# Signal_TX.net
KiCad netlist of a schematic drawn in Altium Designer
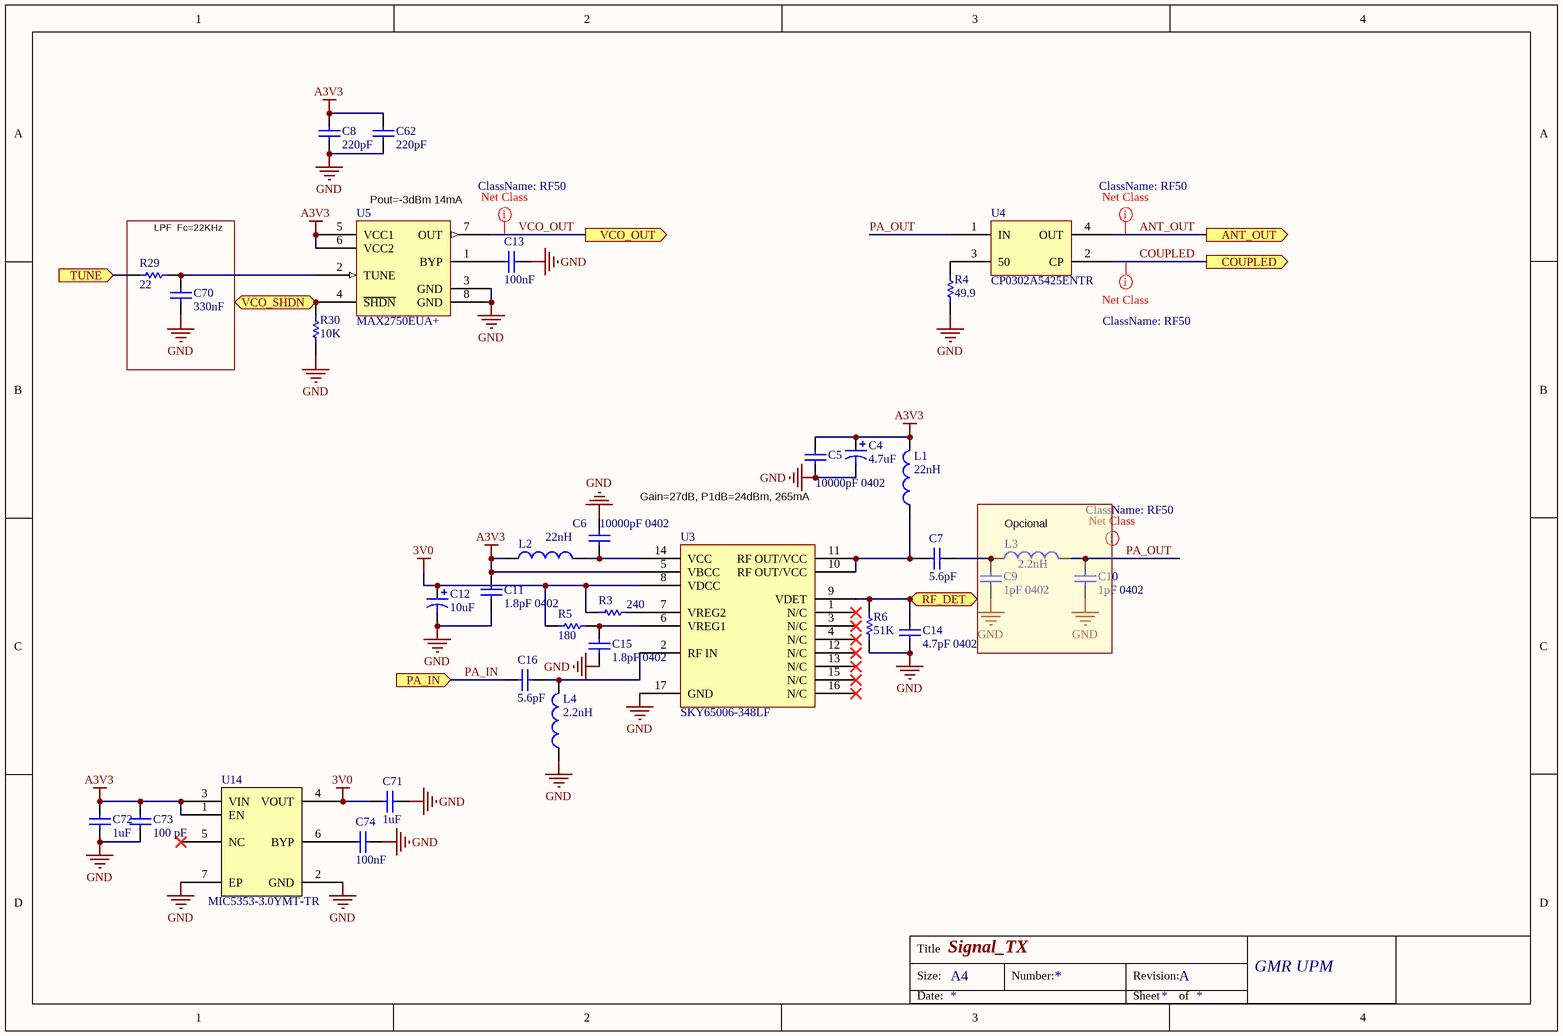
[diagram p0: Signal_TX.SchDoc]

(export (version "E")
  (design (tool "Eeschema 10.0.6"))
  (components
    (comp (ref "C4")
      (value "4.7uF")
      (footprint "0603 Cap")
      (description "CAP TANT 4.7UF 10V 20% 0603")
      (fields
        (field (name "MANUFACTURER") "AVX Corporation")
        (field (name "MANUFACTURER PART NUMBER") "F981A475MMA")
      )
      (libsource (lib "Componentes_base") (part "F981A475MMA"))
    )
    (comp (ref "C5")
      (value "10000pF 0402")
      (footprint "RESC1005X04L")
      (description "CAP CER 10000PF 25V X7R 0402")
      (fields
        (field (name "MANUFACTURER") "Murata Electronics North America")
        (field (name "MANUFACTURER PART NUMBER") "GRM155R71E103KA01J")
      )
      (libsource (lib "Componentes_base") (part "GRM155R71E103KA01J"))
    )
    (comp (ref "C6")
      (value "10000pF 0402")
      (footprint "RESC1005X04L")
      (description "CAP CER 10000PF 25V X7R 0402")
      (fields
        (field (name "MANUFACTURER") "Murata Electronics North America")
        (field (name "MANUFACTURER PART NUMBER") "GRM155R71E103KA01J")
      )
      (libsource (lib "Componentes_base") (part "GRM155R71E103KA01J"))
    )
    (comp (ref "C7")
      (value "5.6pF")
      (footprint "RESC1005X04L")
      (description "AVX - 04025A5R6CAT2A - COND, MLCC, C0G/NP0, 5.6PF, 50V, 0402")
      (fields (field (name "MANUFACTURER") "AVX") (field (name "MANUFACTURER PART NUMBER") "04025A5R6CAT2A"))
      (libsource (lib "Componentes_base") (part "04025A5R6CAT2A"))
    )
    (comp (ref "C8")
      (value "220pF")
      (footprint "0603 Cap")
      (description "CAP CER 220PF 50V X7R 0603")
      (fields
        (field (name "MANUFACTURER") "Samsung Electro-Mechanics America, Inc.")
        (field (name "MANUFACTURER PART NUMBER") "CL10B221KB8WPNC")
      )
      (libsource (lib "Componentes_base") (part "CL10B221KB8WPNC"))
    )
    (comp (ref "C9")
      (value "1pF 0402")
      (footprint "CAPC1005X05L")
      (description "CAP CER 1PF 50V C0G/NP0 0402")
      (libsource (lib "Componentes_base") (part "GRM1555C1H1R0CA01D"))
    )
    (comp (ref "C10")
      (value "1pF 0402")
      (footprint "CAPC1005X05L")
      (description "CAP CER 1PF 50V C0G/NP0 0402")
      (libsource (lib "Componentes_base") (part "GRM1555C1H1R0CA01D"))
    )
    (comp (ref "C11")
      (value "1.8pF 0402")
      (footprint "CAPC1005X05L")
      (description "CAP CER 1.8PF 50V C0G/NP0 0402")
      (fields
        (field (name "MANUFACTURER") "Murata Electronics North America")
        (field (name "MANUFACTURER PART NUMBER") "GRM1555C1H1R8CZ01D")
      )
      (libsource (lib "Componentes_base") (part "GRM1555C1H1R8CZ01D"))
    )
    (comp (ref "C12")
      (value "10uF")
      (footprint "CAPC3216X09L")
      (description "CAP TANT 10UF 6.3V 20% 1206")
      (fields
        (field (name "MANUFACTURER") "AVX Corporation")
        (field (name "MANUFACTURER PART NUMBER") "TAJA106M006RNJ")
      )
      (libsource (lib "Componentes_base") (part "TAJA106M006RNJ"))
    )
    (comp (ref "C13")
      (value "100nF")
      (footprint "0603 Cap")
      (description "CAP CER 0.1UF 16V X7R 0603")
      (fields
        (field (name "MANUFACTURER") "KEMET")
        (field (name "MANUFACTURER PART NUMBER") "C0603C104K4RACTU")
      )
      (libsource (lib "Componentes_base") (part "C0603C104K4RACTU"))
    )
    (comp (ref "C14")
      (value "4.7pF 0402")
      (footprint "RESC1005X04L")
      (description "CAP CER 4.7PF 50V C0G/NP0 0402")
      (fields
        (field (name "MANUFACTURER") "Murata Electronics North America")
        (field (name "MANUFACTURER PART NUMBER") "GRM1555C1H4R7CA01D")
      )
      (libsource (lib "Componentes_base") (part "GRM1555C1H4R7CA01D"))
    )
    (comp (ref "C15")
      (value "1.8pF 0402")
      (footprint "CAPC1005X05L")
      (description "CAP CER 1.8PF 50V C0G/NP0 0402")
      (fields
        (field (name "MANUFACTURER") "Murata Electronics North America")
        (field (name "MANUFACTURER PART NUMBER") "GRM1555C1H1R8CZ01D")
      )
      (libsource (lib "Componentes_base") (part "GRM1555C1H1R8CZ01D"))
    )
    (comp (ref "C16")
      (value "5.6pF")
      (footprint "RESC1005X04L")
      (description "AVX - 04025A5R6CAT2A - COND, MLCC, C0G/NP0, 5.6PF, 50V, 0402")
      (fields (field (name "MANUFACTURER") "AVX") (field (name "MANUFACTURER PART NUMBER") "04025A5R6CAT2A"))
      (libsource (lib "Componentes_base") (part "04025A5R6CAT2A"))
    )
    (comp (ref "C62")
      (value "220pF")
      (footprint "0603 Cap")
      (description "CAP CER 220PF 50V X7R 0603")
      (fields
        (field (name "MANUFACTURER") "Samsung Electro-Mechanics America, Inc.")
        (field (name "MANUFACTURER PART NUMBER") "CL10B221KB8WPNC")
      )
      (libsource (lib "Componentes_base") (part "CL10B221KB8WPNC"))
    )
    (comp (ref "C70")
      (value "330nF")
      (footprint "0603 Cap")
      (description "CAP CER 0.33UF 16V X7R 0603")
      (fields
        (field (name "MANUFACTURER") "Yageo")
        (field (name "MANUFACTURER PART NUMBER") "CC0603KRX7R7BB334")
      )
      (libsource (lib "componentes") (part "CC0603KRX7R7BB334"))
    )
    (comp (ref "C71")
      (value "1uF")
      (footprint "0603 Cap")
      (description "CAP CER 1UF 16V X7R 0603")
      (fields
        (field (name "MANUFACTURER") "Samsung Electro-Mechanics America, Inc.")
        (field (name "MANUFACTURER PART NUMBER") "CL10B105MO8NNWC")
      )
      (libsource (lib "Componentes_base") (part "CL10B105MO8NNWC"))
    )
    (comp (ref "C72")
      (value "1uF")
      (footprint "0603 Cap")
      (description "CAP CER 1UF 16V X7R 0603")
      (fields
        (field (name "MANUFACTURER") "Samsung Electro-Mechanics America, Inc.")
        (field (name "MANUFACTURER PART NUMBER") "CL10B105MO8NNWC")
      )
      (libsource (lib "Componentes_base") (part "CL10B105MO8NNWC"))
    )
    (comp (ref "C73")
      (value "100 pF")
      (footprint "CAPC1005X05L")
      (description "CAP CER 100PF 50V 5% NP0 0402")
      (fields
        (field (name "MANUFACTURER") "Samsung Electro-Mechanics America, Inc")
        (field (name "MANUFACTURER PART NUMBER") "CL05C101JB5NNNC")
      )
      (libsource (lib "Componentes_base") (part "CL05C101JB5NNNC"))
    )
    (comp (ref "C74")
      (value "100nF")
      (footprint "0603 Cap")
      (description "CAP CER 0.1UF 16V X7R 0603")
      (fields
        (field (name "MANUFACTURER") "KEMET")
        (field (name "MANUFACTURER PART NUMBER") "C0603C104K4RACTU")
      )
      (libsource (lib "Componentes_base") (part "C0603C104K4RACTU"))
    )
    (comp (ref "L1")
      (value "22nH")
      (footprint "RESC1005X04L")
      (description "FIXED IND 22NH 200MA 700 MOHM")
      (libsource (lib "Componentes_base") (part "MLK1005S22NJT000"))
    )
    (comp (ref "L2")
      (value "22nH")
      (footprint "RESC1005X04L")
      (description "FIXED IND 22NH 200MA 700 MOHM")
      (libsource (lib "Componentes_base") (part "MLK1005S22NJT000"))
    )
    (comp (ref "L3")
      (value "2.2nH")
      (footprint "RESC1005X04L")
      (description "FIXED IND 2.2NH 500MA 180 MOHM")
      (fields
        (field (name "MANUFACTURER") "TDK Corporation")
        (field (name "MANUFACTURER PART NUMBER") "MLK1005S2N2ST000")
      )
      (libsource (lib "Componentes_base") (part "MLK1005S2N2ST000"))
    )
    (comp (ref "L4")
      (value "2.2nH")
      (footprint "RESC1005X04L")
      (description "FIXED IND 2.2NH 500MA 180 MOHM")
      (fields
        (field (name "MANUFACTURER") "TDK Corporation")
        (field (name "MANUFACTURER PART NUMBER") "MLK1005S2N2ST000")
      )
      (libsource (lib "Componentes_base") (part "MLK1005S2N2ST000"))
    )
    (comp (ref "R3")
      (value "240")
      (footprint "RESC1005X04L")
      (description "RES SMD 240 OHM 5% 1/10W 0402")
      (fields
        (field (name "MANUFACTURER") "Panasonic Electronic Components")
        (field (name "MANUFACTURER PART NUMBER") "ERJ-2GEJ241X")
      )
      (libsource (lib "Componentes_base") (part "ERJ-2GEJ241X"))
    )
    (comp (ref "R4")
      (value "49.9")
      (footprint "RESC1005X04L")
      (description "RES 49.9 OHM 1/16W 1% 0402 SMD")
      (fields
        (field (name "MANUFACTURER") "Rohm Semiconductor")
        (field (name "MANUFACTURER PART NUMBER") "MCR01MRTF49R9")
      )
      (libsource (lib "Componentes_base") (part "MCR01MRTF49R9"))
    )
    (comp (ref "R5")
      (value "180")
      (footprint "RESC1005X04L")
      (description "RES SMD 180 OHM 5% 1/10W 0402")
      (libsource (lib "Componentes_base") (part "ERJ-2GEJ181X"))
    )
    (comp (ref "R6")
      (value "51K")
      (footprint "RESC1005X04L")
      (description "RES SMD 51K OHM 5% 1/10W 0402")
      (fields
        (field (name "MANUFACTURER") "Panasonic Electronic Components")
        (field (name "MANUFACTURER PART NUMBER") "ERJ-2GEJ513X")
      )
      (libsource (lib "Componentes_base") (part "ERJ-2GEJ513X"))
    )
    (comp (ref "R29")
      (value "22")
      (footprint "0603 Res")
      (description "RES SMD 22 OHM 1% 1/10W 0603")
      (fields
        (field (name "MANUFACTURER") "Yageo")
        (field (name "MANUFACTURER PART NUMBER") "RC0603FR-0722RL")
      )
      (libsource (lib "Componentes_base") (part "RC0603FR-0722RL"))
    )
    (comp (ref "R30")
      (value "10K")
      (footprint "0603 Res")
      (description "RES SMD 10K OHM 1% 1/10W 0603")
      (fields
        (field (name "MANUFACTURER") "Yageo")
        (field (name "MANUFACTURER PART NUMBER") "RC0603FR-0710KL")
      )
      (libsource (lib "Componentes_base") (part "RC0603FR-0710KL"))
    )
    (comp (ref "U3")
      (value "SKY65006-348LF")
      (footprint "QFN50P300X300X100_HS-17N")
      (fields
        (field (name "MANUFACTURER") "Broadcom Limited")
        (field (name "MANUFACTURER PART NUMBER") "MGA-13216-BLKG")
      )
      (libsource (lib "Componentes_base") (part "SKY65006-348LF"))
    )
    (comp (ref "U4")
      (value "CP0302A5425ENTR")
      (footprint "DFN60P65X25-4N")
      (description "WIFI COUPLER 0302")
      (fields (field (name "MANUFACTURER") "AVX Corporation"))
      (libsource (lib "Componentes_base") (part "CP0302A5425ENTR"))
    )
    (comp (ref "U5")
      (value "MAX2750EUA+")
      (footprint "uSOP-8 uMAX")
      (description "IC OSC VOLT CNTRL 8-UMAX")
      (fields (field (name "MANUFACTURER") "Maxim Integrated"))
      (libsource (lib "Componentes_base") (part "MAX2750EUA+"))
    )
    (comp (ref "U14")
      (value "MIC5353-3.0YMT-TR")
      (footprint "SON50P160X55_HS-7N")
      (description "IC REG LINEAR 3V 500MA 6TMLF")
      (fields (field (name "MANUFACTURER") "Microchip Technology"))
      (libsource (lib "Componentes_base") (part "MIC5353-3.0YMT-TR"))
    )
  )
  (nets
    (net (code "1") (name "/ANT_OUT") (class "Default")
      (node (ref "U4") (pin "4") (pinfunction "OUT_4") (pintype "passive"))
    )
    (net (code "2") (name "/COUPLED") (class "Default")
      (node (ref "U4") (pin "2") (pinfunction "CP_2") (pintype "passive"))
    )
    (net (code "3") (name "/PA_IN") (class "Default")
      (node (ref "C16") (pin "1") (pinfunction "1_1") (pintype "passive"))
    )
    (net (code "4") (name "/PA_OUT") (class "Default")
      (node (ref "C10") (pin "2") (pinfunction "2_2") (pintype "passive"))
      (node (ref "L3") (pin "2") (pinfunction "2_2") (pintype "passive"))
      (node (ref "U4") (pin "1") (pinfunction "IN_1") (pintype "passive"))
    )
    (net (code "5") (name "/RF_DET") (class "Default")
      (node (ref "C14") (pin "2") (pinfunction "2_2") (pintype "passive"))
      (node (ref "R6") (pin "2") (pinfunction "2_2") (pintype "passive"))
      (node (ref "U3") (pin "9") (pinfunction "VDET_9") (pintype "passive"))
    )
    (net (code "6") (name "/TUNE") (class "Default")
      (node (ref "R29") (pin "1") (pinfunction "1_1") (pintype "passive"))
    )
    (net (code "7") (name "/VCO_OUT") (class "Default")
      (node (ref "U5") (pin "7") (pinfunction "OUT_7") (pintype "output"))
    )
    (net (code "8") (name "/VCO_SHDN") (class "Default")
      (node (ref "R30") (pin "2") (pinfunction "2_2") (pintype "passive"))
      (node (ref "U5") (pin "4") (pinfunction "~{SHDN}_4") (pintype "passive"))
    )
    (net (code "9") (name "3V0") (class "Default")
      (node (ref "C12") (pin "1") (pinfunction "1_1") (pintype "passive"))
      (node (ref "C71") (pin "1") (pinfunction "1_1") (pintype "passive"))
      (node (ref "R3") (pin "2") (pinfunction "2_2") (pintype "passive"))
      (node (ref "R5") (pin "2") (pinfunction "2_2") (pintype "passive"))
      (node (ref "U14") (pin "4") (pinfunction "VOUT_4") (pintype "passive"))
      (node (ref "U3") (pin "8") (pinfunction "VDCC_8") (pintype "passive"))
    )
    (net (code "10") (name "A3V3") (class "Default")
      (node (ref "C11") (pin "2") (pinfunction "2_2") (pintype "passive"))
      (node (ref "C4") (pin "1") (pinfunction "1_1") (pintype "passive"))
      (node (ref "C5") (pin "2") (pinfunction "2_2") (pintype "passive"))
      (node (ref "C62") (pin "2") (pinfunction "2_2") (pintype "passive"))
      (node (ref "C72") (pin "2") (pinfunction "2_2") (pintype "passive"))
      (node (ref "C73") (pin "2") (pinfunction "2_2") (pintype "passive"))
      (node (ref "C8") (pin "2") (pinfunction "2_2") (pintype "passive"))
      (node (ref "L1") (pin "2") (pinfunction "2_2") (pintype "passive"))
      (node (ref "L2") (pin "1") (pinfunction "1_1") (pintype "passive"))
      (node (ref "U14") (pin "1") (pinfunction "EN_1") (pintype "passive"))
      (node (ref "U14") (pin "3") (pinfunction "VIN_3") (pintype "passive"))
      (node (ref "U3") (pin "5") (pinfunction "VBCC_5") (pintype "passive"))
      (node (ref "U5") (pin "5") (pinfunction "VCC1_5") (pintype "passive"))
      (node (ref "U5") (pin "6") (pinfunction "VCC2_6") (pintype "passive"))
    )
    (net (code "11") (name "GND") (class "Default")
      (node (ref "C10") (pin "1") (pinfunction "1_1") (pintype "passive"))
      (node (ref "C11") (pin "1") (pinfunction "1_1") (pintype "passive"))
      (node (ref "C12") (pin "2") (pinfunction "2_2") (pintype "passive"))
      (node (ref "C13") (pin "1") (pinfunction "1_1") (pintype "passive"))
      (node (ref "C14") (pin "1") (pinfunction "1_1") (pintype "passive"))
      (node (ref "C15") (pin "1") (pinfunction "1_1") (pintype "passive"))
      (node (ref "C4") (pin "2") (pinfunction "2_2") (pintype "passive"))
      (node (ref "C5") (pin "1") (pinfunction "1_1") (pintype "passive"))
      (node (ref "C6") (pin "2") (pinfunction "2_2") (pintype "passive"))
      (node (ref "C62") (pin "1") (pinfunction "1_1") (pintype "passive"))
      (node (ref "C70") (pin "1") (pinfunction "1_1") (pintype "passive"))
      (node (ref "C71") (pin "2") (pinfunction "2_2") (pintype "passive"))
      (node (ref "C72") (pin "1") (pinfunction "1_1") (pintype "passive"))
      (node (ref "C73") (pin "1") (pinfunction "1_1") (pintype "passive"))
      (node (ref "C74") (pin "2") (pinfunction "2_2") (pintype "passive"))
      (node (ref "C8") (pin "1") (pinfunction "1_1") (pintype "passive"))
      (node (ref "C9") (pin "1") (pinfunction "1_1") (pintype "passive"))
      (node (ref "L4") (pin "1") (pinfunction "1_1") (pintype "passive"))
      (node (ref "R30") (pin "1") (pinfunction "1_1") (pintype "passive"))
      (node (ref "R4") (pin "1") (pinfunction "1_1") (pintype "passive"))
      (node (ref "R6") (pin "1") (pinfunction "1_1") (pintype "passive"))
      (node (ref "U14") (pin "2") (pinfunction "GND_2") (pintype "passive"))
      (node (ref "U14") (pin "7") (pinfunction "EP_7") (pintype "passive"))
      (node (ref "U3") (pin "17") (pinfunction "GND_17") (pintype "passive"))
      (node (ref "U5") (pin "3") (pinfunction "GND_3") (pintype "passive"))
      (node (ref "U5") (pin "8") (pinfunction "GND_8") (pintype "passive"))
    )
    (net (code "12") (name "Net-(C7-Pad1)") (class "Default")
      (node (ref "C7") (pin "1") (pinfunction "1_1") (pintype "passive"))
      (node (ref "L1") (pin "1") (pinfunction "1_1") (pintype "passive"))
      (node (ref "U3") (pin "10") (pinfunction "RF_OUT/VCC_10") (pintype "passive"))
      (node (ref "U3") (pin "11") (pinfunction "RF_OUT/VCC_11") (pintype "passive"))
    )
    (net (code "13") (name "Net-(C7-Pad2)") (class "Default")
      (node (ref "C7") (pin "2") (pinfunction "2_2") (pintype "passive"))
      (node (ref "C9") (pin "2") (pinfunction "2_2") (pintype "passive"))
      (node (ref "L3") (pin "1") (pinfunction "1_1") (pintype "passive"))
    )
    (net (code "14") (name "Net-(U3-RF_IN)") (class "Default")
      (node (ref "C16") (pin "2") (pinfunction "2_2") (pintype "passive"))
      (node (ref "L4") (pin "2") (pinfunction "2_2") (pintype "passive"))
      (node (ref "U3") (pin "2") (pinfunction "RF_IN_2") (pintype "passive"))
    )
    (net (code "15") (name "Net-(U3-VCC)") (class "Default")
      (node (ref "C6") (pin "1") (pinfunction "1_1") (pintype "passive"))
      (node (ref "L2") (pin "2") (pinfunction "2_2") (pintype "passive"))
      (node (ref "U3") (pin "14") (pinfunction "VCC_14") (pintype "passive"))
    )
    (net (code "16") (name "Net-(U3-VREG1)") (class "Default")
      (node (ref "C15") (pin "2") (pinfunction "2_2") (pintype "passive"))
      (node (ref "R5") (pin "1") (pinfunction "1_1") (pintype "passive"))
      (node (ref "U3") (pin "6") (pinfunction "VREG1_6") (pintype "passive"))
    )
    (net (code "17") (name "Net-(U3-VREG2)") (class "Default")
      (node (ref "R3") (pin "1") (pinfunction "1_1") (pintype "passive"))
      (node (ref "U3") (pin "7") (pinfunction "VREG2_7") (pintype "passive"))
    )
    (net (code "18") (name "Net-(U4-50)") (class "Default")
      (node (ref "R4") (pin "2") (pinfunction "2_2") (pintype "passive"))
      (node (ref "U4") (pin "3") (pinfunction "50_3") (pintype "passive"))
    )
    (net (code "19") (name "Net-(U5-BYP)") (class "Default")
      (node (ref "C13") (pin "2") (pinfunction "2_2") (pintype "passive"))
      (node (ref "U5") (pin "1") (pinfunction "BYP_1") (pintype "passive"))
    )
    (net (code "20") (name "Net-(U5-TUNE)") (class "Default")
      (node (ref "C70") (pin "2") (pinfunction "2_2") (pintype "passive"))
      (node (ref "R29") (pin "2") (pinfunction "2_2") (pintype "passive"))
      (node (ref "U5") (pin "2") (pinfunction "TUNE_2") (pintype "input"))
    )
    (net (code "21") (name "Net-(U14-BYP)") (class "Default")
      (node (ref "C74") (pin "1") (pinfunction "1_1") (pintype "passive"))
      (node (ref "U14") (pin "6") (pinfunction "BYP_6") (pintype "passive"))
    )
    (net (code "22") (name "unconnected-(U3-N{slash}C-Pad1)") (class "Default")
      (node (ref "U3") (pin "1") (pinfunction "N/C_1") (pintype "passive+no_connect"))
    )
    (net (code "23") (name "unconnected-(U3-N{slash}C-Pad3)") (class "Default")
      (node (ref "U3") (pin "3") (pinfunction "N/C_3") (pintype "passive+no_connect"))
    )
    (net (code "24") (name "unconnected-(U3-N{slash}C-Pad4)") (class "Default")
      (node (ref "U3") (pin "4") (pinfunction "N/C_4") (pintype "passive+no_connect"))
    )
    (net (code "25") (name "unconnected-(U3-N{slash}C-Pad12)") (class "Default")
      (node (ref "U3") (pin "12") (pinfunction "N/C_12") (pintype "passive+no_connect"))
    )
    (net (code "26") (name "unconnected-(U3-N{slash}C-Pad13)") (class "Default")
      (node (ref "U3") (pin "13") (pinfunction "N/C_13") (pintype "passive+no_connect"))
    )
    (net (code "27") (name "unconnected-(U3-N{slash}C-Pad15)") (class "Default")
      (node (ref "U3") (pin "15") (pinfunction "N/C_15") (pintype "passive+no_connect"))
    )
    (net (code "28") (name "unconnected-(U3-N{slash}C-Pad16)") (class "Default")
      (node (ref "U3") (pin "16") (pinfunction "N/C_16") (pintype "passive+no_connect"))
    )
    (net (code "29") (name "unconnected-(U14-NC-Pad5)") (class "Default")
      (node (ref "U14") (pin "5") (pinfunction "NC_5") (pintype "passive+no_connect"))
    )
  )
)
